# FX-Devcart_rev_A.net
KiCad netlist of a schematic drawn in EAGLE
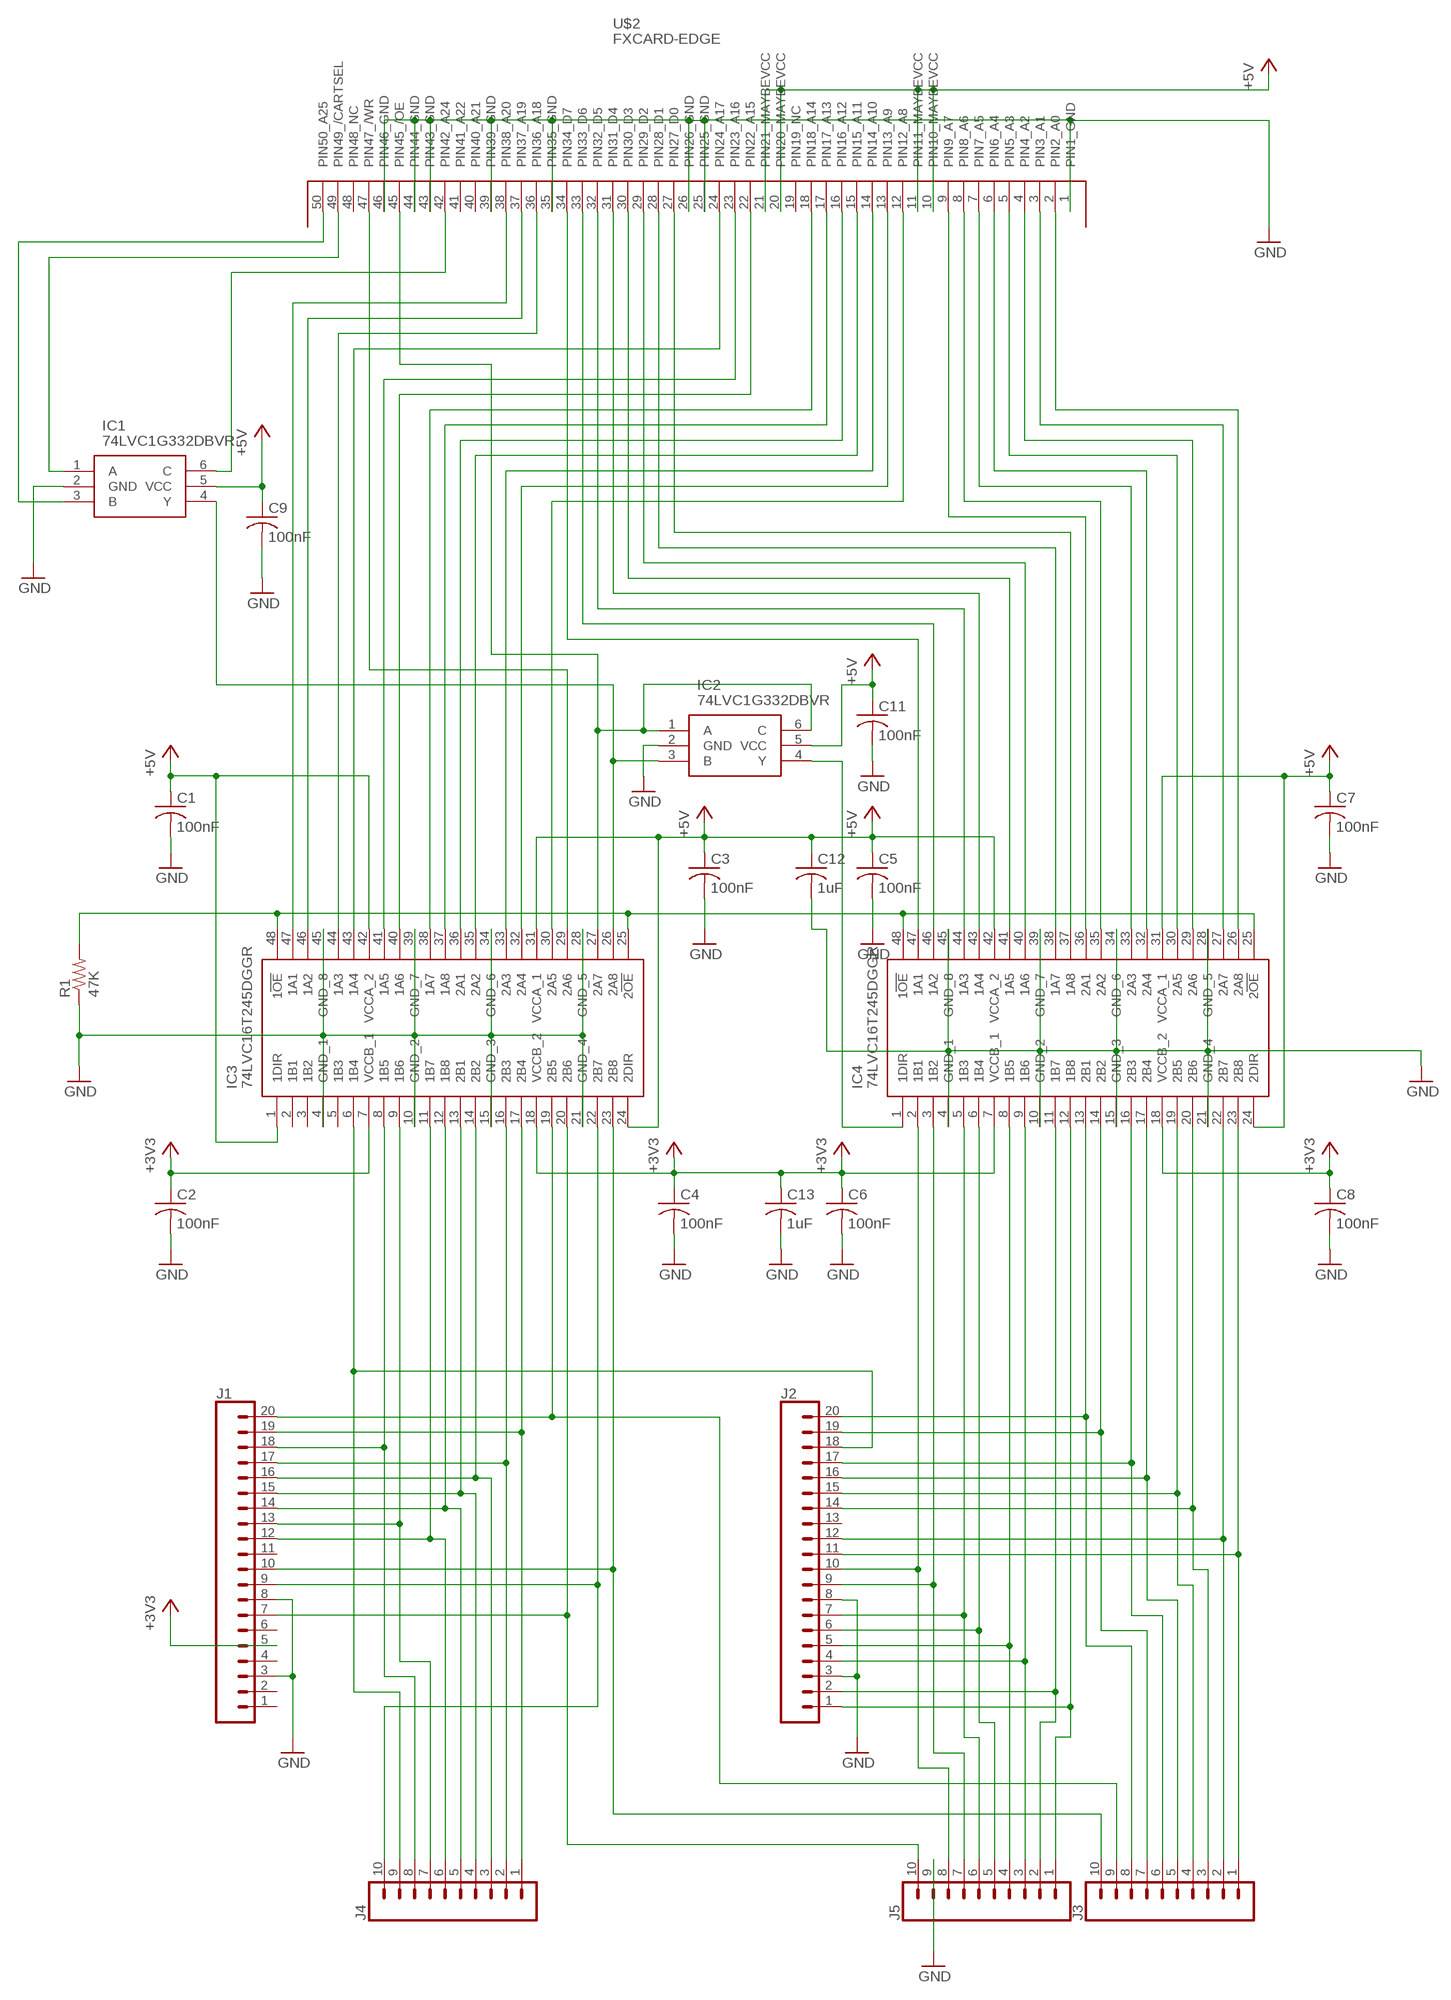
[diagram p0: schematic, sheet 1]

(export (version "E")
  (design (tool "Eeschema 10.0.6"))
  (components
    (comp (ref "C1")
      (value "100nF")
      (footprint "eagle-import:C0402")
      (libsource (lib "eagle-import") (part "C-USC0402"))
    )
    (comp (ref "C2")
      (value "100nF")
      (footprint "eagle-import:C0402")
      (libsource (lib "eagle-import") (part "C-USC0402"))
    )
    (comp (ref "C3")
      (value "100nF")
      (footprint "eagle-import:C0402")
      (libsource (lib "eagle-import") (part "C-USC0402"))
    )
    (comp (ref "C4")
      (value "100nF")
      (footprint "eagle-import:C0402")
      (libsource (lib "eagle-import") (part "C-USC0402"))
    )
    (comp (ref "C5")
      (value "100nF")
      (footprint "eagle-import:C0402")
      (libsource (lib "eagle-import") (part "C-USC0402"))
    )
    (comp (ref "C6")
      (value "100nF")
      (footprint "eagle-import:C0402")
      (libsource (lib "eagle-import") (part "C-USC0402"))
    )
    (comp (ref "C7")
      (value "100nF")
      (footprint "eagle-import:C0402")
      (libsource (lib "eagle-import") (part "C-USC0402"))
    )
    (comp (ref "C8")
      (value "100nF")
      (footprint "eagle-import:C0402")
      (libsource (lib "eagle-import") (part "C-USC0402"))
    )
    (comp (ref "C9")
      (value "100nF")
      (footprint "eagle-import:C0402")
      (libsource (lib "eagle-import") (part "C-USC0402"))
    )
    (comp (ref "C11")
      (value "100nF")
      (footprint "eagle-import:C0402")
      (libsource (lib "eagle-import") (part "C-USC0402"))
    )
    (comp (ref "C12")
      (value "1uF")
      (footprint "eagle-import:C0402")
      (libsource (lib "eagle-import") (part "C-USC0402"))
    )
    (comp (ref "C13")
      (value "1uF")
      (footprint "eagle-import:C0402")
      (libsource (lib "eagle-import") (part "C-USC0402"))
    )
    (comp (ref "IC1")
      (value "74LVC1G332DBVR")
      (footprint "eagle-import:SOT95P280X145-6N")
      (libsource (lib "eagle-import") (part "74LVC1G332DBVR"))
    )
    (comp (ref "IC2")
      (value "74LVC1G332DBVR")
      (footprint "eagle-import:SOT95P280X145-6N")
      (libsource (lib "eagle-import") (part "74LVC1G332DBVR"))
    )
    (comp (ref "IC3")
      (value "74LVC16T245DGGR")
      (footprint "eagle-import:SOP50P810X120-48N")
      (libsource (lib "eagle-import") (part "74LVC16T245DGGR"))
    )
    (comp (ref "IC4")
      (value "74LVC16T245DGGR")
      (footprint "eagle-import:SOP50P810X120-48N")
      (libsource (lib "eagle-import") (part "74LVC16T245DGGR"))
    )
    (comp (ref "J1")
      (value "CONN_20NOSILK")
      (footprint "eagle-import:1X20_NOSILK")
      (libsource (lib "eagle-import") (part "CONN_20NOSILK"))
    )
    (comp (ref "J2")
      (value "CONN_20NOSILK")
      (footprint "eagle-import:1X20_NOSILK")
      (libsource (lib "eagle-import") (part "CONN_20NOSILK"))
    )
    (comp (ref "J3")
      (value "CONN_10NO_SILK_PTH_FEMALE")
      (footprint "eagle-import:1X10_NO_SILK")
      (libsource (lib "eagle-import") (part "CONN_10NO_SILK_PTH_FEMALE"))
    )
    (comp (ref "J4")
      (value "CONN_10NO_SILK_PTH_FEMALE")
      (footprint "eagle-import:1X10_NO_SILK")
      (libsource (lib "eagle-import") (part "CONN_10NO_SILK_PTH_FEMALE"))
    )
    (comp (ref "J5")
      (value "CONN_10NO_SILK_PTH_FEMALE")
      (footprint "eagle-import:1X10_NO_SILK")
      (libsource (lib "eagle-import") (part "CONN_10NO_SILK_PTH_FEMALE"))
    )
    (comp (ref "R1")
      (value "47K")
      (footprint "eagle-import:R0402")
      (libsource (lib "eagle-import") (part "R-US_R0402"))
    )
    (comp (ref "U$2")
      (value "FXCARD-EDGE")
      (footprint "eagle-import:FXCARD-EDGE")
      (libsource (lib "eagle-import") (part "FXCARD-EDGE"))
    )
  )
  (nets
    (net (code "1") (name "+3V3") (class "Default")
      (node (ref "C13") (pin "1") (pinfunction "1_1") (pintype "passive"))
      (node (ref "C2") (pin "1") (pinfunction "1_1") (pintype "passive"))
      (node (ref "C4") (pin "1") (pinfunction "1_1") (pintype "passive"))
      (node (ref "C6") (pin "1") (pinfunction "1_1") (pintype "passive"))
      (node (ref "C8") (pin "1") (pinfunction "1_1") (pintype "passive"))
      (node (ref "IC3") (pin "18") (pinfunction "VCCB_2_18") (pintype "bidirectional"))
      (node (ref "IC3") (pin "7") (pinfunction "VCCB_1_7") (pintype "bidirectional"))
      (node (ref "IC4") (pin "18") (pinfunction "VCCB_2_18") (pintype "bidirectional"))
      (node (ref "IC4") (pin "7") (pinfunction "VCCB_1_7") (pintype "bidirectional"))
      (node (ref "J1") (pin "5") (pinfunction "5_5") (pintype "passive"))
    )
    (net (code "2") (name "+5V") (class "Default")
      (node (ref "C1") (pin "1") (pinfunction "1_1") (pintype "passive"))
      (node (ref "C11") (pin "1") (pinfunction "1_1") (pintype "passive"))
      (node (ref "C12") (pin "1") (pinfunction "1_1") (pintype "passive"))
      (node (ref "C3") (pin "1") (pinfunction "1_1") (pintype "passive"))
      (node (ref "C5") (pin "1") (pinfunction "1_1") (pintype "passive"))
      (node (ref "C7") (pin "1") (pinfunction "1_1") (pintype "passive"))
      (node (ref "C9") (pin "1") (pinfunction "1_1") (pintype "passive"))
      (node (ref "IC1") (pin "5") (pinfunction "VCC_5") (pintype "bidirectional"))
      (node (ref "IC2") (pin "5") (pinfunction "VCC_5") (pintype "bidirectional"))
      (node (ref "IC3") (pin "1") (pinfunction "1DIR_1") (pintype "bidirectional"))
      (node (ref "IC3") (pin "24") (pinfunction "2DIR_24") (pintype "bidirectional"))
      (node (ref "IC3") (pin "31") (pinfunction "VCCA_1_31") (pintype "bidirectional"))
      (node (ref "IC3") (pin "42") (pinfunction "VCCA_2_42") (pintype "bidirectional"))
      (node (ref "IC4") (pin "24") (pinfunction "2DIR_24") (pintype "bidirectional"))
      (node (ref "IC4") (pin "31") (pinfunction "VCCA_1_31") (pintype "bidirectional"))
      (node (ref "IC4") (pin "42") (pinfunction "VCCA_2_42") (pintype "bidirectional"))
      (node (ref "U$2") (pin "10") (pinfunction "PIN10_MAYBEVCC_10") (pintype "bidirectional"))
      (node (ref "U$2") (pin "11") (pinfunction "PIN11_MAYBEVCC_11") (pintype "bidirectional"))
      (node (ref "U$2") (pin "20") (pinfunction "PIN20_MAYBEVCC_20") (pintype "bidirectional"))
      (node (ref "U$2") (pin "21") (pinfunction "PIN21_MAYBEVCC_21") (pintype "bidirectional"))
    )
    (net (code "3") (name "GND") (class "Default")
      (node (ref "C1") (pin "2") (pinfunction "2_2") (pintype "passive"))
      (node (ref "C11") (pin "2") (pinfunction "2_2") (pintype "passive"))
      (node (ref "C12") (pin "2") (pinfunction "2_2") (pintype "passive"))
      (node (ref "C13") (pin "2") (pinfunction "2_2") (pintype "passive"))
      (node (ref "C2") (pin "2") (pinfunction "2_2") (pintype "passive"))
      (node (ref "C3") (pin "2") (pinfunction "2_2") (pintype "passive"))
      (node (ref "C4") (pin "2") (pinfunction "2_2") (pintype "passive"))
      (node (ref "C5") (pin "2") (pinfunction "2_2") (pintype "passive"))
      (node (ref "C6") (pin "2") (pinfunction "2_2") (pintype "passive"))
      (node (ref "C7") (pin "2") (pinfunction "2_2") (pintype "passive"))
      (node (ref "C8") (pin "2") (pinfunction "2_2") (pintype "passive"))
      (node (ref "C9") (pin "2") (pinfunction "2_2") (pintype "passive"))
      (node (ref "IC1") (pin "2") (pinfunction "GND_2") (pintype "bidirectional"))
      (node (ref "IC2") (pin "2") (pinfunction "GND_2") (pintype "bidirectional"))
      (node (ref "IC3") (pin "10") (pinfunction "GND_2_10") (pintype "bidirectional"))
      (node (ref "IC3") (pin "15") (pinfunction "GND_3_15") (pintype "bidirectional"))
      (node (ref "IC3") (pin "21") (pinfunction "GND_4_21") (pintype "bidirectional"))
      (node (ref "IC3") (pin "28") (pinfunction "GND_5_28") (pintype "bidirectional"))
      (node (ref "IC3") (pin "34") (pinfunction "GND_6_34") (pintype "bidirectional"))
      (node (ref "IC3") (pin "39") (pinfunction "GND_7_39") (pintype "bidirectional"))
      (node (ref "IC3") (pin "4") (pinfunction "GND_1_4") (pintype "bidirectional"))
      (node (ref "IC3") (pin "45") (pinfunction "GND_8_45") (pintype "bidirectional"))
      (node (ref "IC4") (pin "10") (pinfunction "GND_2_10") (pintype "bidirectional"))
      (node (ref "IC4") (pin "15") (pinfunction "GND_3_15") (pintype "bidirectional"))
      (node (ref "IC4") (pin "21") (pinfunction "GND_4_21") (pintype "bidirectional"))
      (node (ref "IC4") (pin "28") (pinfunction "GND_5_28") (pintype "bidirectional"))
      (node (ref "IC4") (pin "34") (pinfunction "GND_6_34") (pintype "bidirectional"))
      (node (ref "IC4") (pin "39") (pinfunction "GND_7_39") (pintype "bidirectional"))
      (node (ref "IC4") (pin "4") (pinfunction "GND_1_4") (pintype "bidirectional"))
      (node (ref "IC4") (pin "45") (pinfunction "GND_8_45") (pintype "bidirectional"))
      (node (ref "J1") (pin "3") (pinfunction "3_3") (pintype "passive"))
      (node (ref "J1") (pin "8") (pinfunction "8_8") (pintype "passive"))
      (node (ref "J2") (pin "3") (pinfunction "3_3") (pintype "passive"))
      (node (ref "J2") (pin "8") (pinfunction "8_8") (pintype "passive"))
      (node (ref "J5") (pin "9") (pinfunction "9_9") (pintype "passive"))
      (node (ref "R1") (pin "1") (pinfunction "1_1") (pintype "passive"))
      (node (ref "U$2") (pin "1") (pinfunction "PIN1_GND_1") (pintype "power_in"))
      (node (ref "U$2") (pin "25") (pinfunction "PIN25_GND_25") (pintype "power_in"))
      (node (ref "U$2") (pin "26") (pinfunction "PIN26_GND_26") (pintype "power_in"))
      (node (ref "U$2") (pin "35") (pinfunction "PIN35_GND_35") (pintype "power_in"))
      (node (ref "U$2") (pin "39") (pinfunction "PIN39_GND_39") (pintype "power_in"))
      (node (ref "U$2") (pin "43") (pinfunction "PIN43_GND_43") (pintype "power_in"))
      (node (ref "U$2") (pin "44") (pinfunction "PIN44_GND_44") (pintype "power_in"))
      (node (ref "U$2") (pin "46") (pinfunction "PIN46_GND_46") (pintype "power_in"))
    )
    (net (code "4") (name "Net-(IC1-A)") (class "Default")
      (node (ref "IC1") (pin "1") (pinfunction "A_1") (pintype "bidirectional"))
      (node (ref "U$2") (pin "49") (pinfunction "PIN49_/CARTSEL_49") (pintype "bidirectional"))
    )
    (net (code "5") (name "Net-(IC1-B)") (class "Default")
      (node (ref "IC1") (pin "3") (pinfunction "B_3") (pintype "bidirectional"))
      (node (ref "U$2") (pin "50") (pinfunction "PIN50_A25_50") (pintype "bidirectional"))
    )
    (net (code "6") (name "Net-(IC1-C)") (class "Default")
      (node (ref "IC1") (pin "6") (pinfunction "C_6") (pintype "bidirectional"))
      (node (ref "U$2") (pin "42") (pinfunction "PIN42_A24_42") (pintype "bidirectional"))
    )
    (net (code "7") (name "Net-(IC1-Y)") (class "Default")
      (node (ref "IC1") (pin "4") (pinfunction "Y_4") (pintype "bidirectional"))
      (node (ref "IC2") (pin "3") (pinfunction "B_3") (pintype "bidirectional"))
      (node (ref "IC3") (pin "26") (pinfunction "2A8_26") (pintype "bidirectional"))
    )
    (net (code "8") (name "Net-(IC2-A)") (class "Default")
      (node (ref "IC2") (pin "1") (pinfunction "A_1") (pintype "bidirectional"))
      (node (ref "IC2") (pin "6") (pinfunction "C_6") (pintype "bidirectional"))
      (node (ref "IC3") (pin "27") (pinfunction "2A7_27") (pintype "bidirectional"))
      (node (ref "U$2") (pin "45") (pinfunction "PIN45_/OE_45") (pintype "bidirectional"))
    )
    (net (code "9") (name "Net-(IC2-Y)") (class "Default")
      (node (ref "IC2") (pin "4") (pinfunction "Y_4") (pintype "bidirectional"))
      (node (ref "IC4") (pin "1") (pinfunction "1DIR_1") (pintype "bidirectional"))
    )
    (net (code "10") (name "Net-(IC3-1A1)") (class "Default")
      (node (ref "IC3") (pin "47") (pinfunction "1A1_47") (pintype "bidirectional"))
      (node (ref "U$2") (pin "38") (pinfunction "PIN38_A20_38") (pintype "bidirectional"))
    )
    (net (code "11") (name "Net-(IC3-1A2)") (class "Default")
      (node (ref "IC3") (pin "46") (pinfunction "1A2_46") (pintype "bidirectional"))
      (node (ref "U$2") (pin "37") (pinfunction "PIN37_A19_37") (pintype "bidirectional"))
    )
    (net (code "12") (name "Net-(IC3-1A3)") (class "Default")
      (node (ref "IC3") (pin "44") (pinfunction "1A3_44") (pintype "bidirectional"))
      (node (ref "U$2") (pin "36") (pinfunction "PIN36_A18_36") (pintype "bidirectional"))
    )
    (net (code "13") (name "Net-(IC3-1A4)") (class "Default")
      (node (ref "IC3") (pin "43") (pinfunction "1A4_43") (pintype "bidirectional"))
      (node (ref "U$2") (pin "24") (pinfunction "PIN24_A17_24") (pintype "bidirectional"))
    )
    (net (code "14") (name "Net-(IC3-1A5)") (class "Default")
      (node (ref "IC3") (pin "41") (pinfunction "1A5_41") (pintype "bidirectional"))
      (node (ref "U$2") (pin "23") (pinfunction "PIN23_A16_23") (pintype "bidirectional"))
    )
    (net (code "15") (name "Net-(IC3-1A6)") (class "Default")
      (node (ref "IC3") (pin "40") (pinfunction "1A6_40") (pintype "bidirectional"))
      (node (ref "U$2") (pin "22") (pinfunction "PIN22_A15_22") (pintype "bidirectional"))
    )
    (net (code "16") (name "Net-(IC3-1A7)") (class "Default")
      (node (ref "IC3") (pin "38") (pinfunction "1A7_38") (pintype "bidirectional"))
      (node (ref "U$2") (pin "18") (pinfunction "PIN18_A14_18") (pintype "bidirectional"))
    )
    (net (code "17") (name "Net-(IC3-1A8)") (class "Default")
      (node (ref "IC3") (pin "37") (pinfunction "1A8_37") (pintype "bidirectional"))
      (node (ref "U$2") (pin "17") (pinfunction "PIN17_A13_17") (pintype "bidirectional"))
    )
    (net (code "18") (name "Net-(IC3-1B4)") (class "Default")
      (node (ref "IC3") (pin "6") (pinfunction "1B4_6") (pintype "bidirectional"))
      (node (ref "J2") (pin "18") (pinfunction "18_18") (pintype "passive"))
      (node (ref "J4") (pin "9") (pinfunction "9_9") (pintype "passive"))
    )
    (net (code "19") (name "Net-(IC3-1B5)") (class "Default")
      (node (ref "IC3") (pin "8") (pinfunction "1B5_8") (pintype "bidirectional"))
      (node (ref "J1") (pin "18") (pinfunction "18_18") (pintype "passive"))
      (node (ref "J4") (pin "8") (pinfunction "8_8") (pintype "passive"))
    )
    (net (code "20") (name "Net-(IC3-1B6)") (class "Default")
      (node (ref "IC3") (pin "9") (pinfunction "1B6_9") (pintype "bidirectional"))
      (node (ref "J1") (pin "13") (pinfunction "13_13") (pintype "passive"))
      (node (ref "J4") (pin "7") (pinfunction "7_7") (pintype "passive"))
    )
    (net (code "21") (name "Net-(IC3-1B7)") (class "Default")
      (node (ref "IC3") (pin "11") (pinfunction "1B7_11") (pintype "bidirectional"))
      (node (ref "J1") (pin "12") (pinfunction "12_12") (pintype "passive"))
      (node (ref "J4") (pin "6") (pinfunction "6_6") (pintype "passive"))
    )
    (net (code "22") (name "Net-(IC3-1B8)") (class "Default")
      (node (ref "IC3") (pin "12") (pinfunction "1B8_12") (pintype "bidirectional"))
      (node (ref "J1") (pin "14") (pinfunction "14_14") (pintype "passive"))
      (node (ref "J4") (pin "5") (pinfunction "5_5") (pintype "passive"))
    )
    (net (code "23") (name "Net-(IC3-1~{OE})") (class "Default")
      (node (ref "IC3") (pin "25") (pinfunction "2~{OE}_25") (pintype "bidirectional"))
      (node (ref "IC3") (pin "48") (pinfunction "1~{OE}_48") (pintype "bidirectional"))
      (node (ref "IC4") (pin "25") (pinfunction "2~{OE}_25") (pintype "bidirectional"))
      (node (ref "IC4") (pin "48") (pinfunction "1~{OE}_48") (pintype "bidirectional"))
      (node (ref "R1") (pin "2") (pinfunction "2_2") (pintype "passive"))
    )
    (net (code "24") (name "Net-(IC3-2A1)") (class "Default")
      (node (ref "IC3") (pin "36") (pinfunction "2A1_36") (pintype "bidirectional"))
      (node (ref "U$2") (pin "16") (pinfunction "PIN16_A12_16") (pintype "bidirectional"))
    )
    (net (code "25") (name "Net-(IC3-2A2)") (class "Default")
      (node (ref "IC3") (pin "35") (pinfunction "2A2_35") (pintype "bidirectional"))
      (node (ref "U$2") (pin "15") (pinfunction "PIN15_A11_15") (pintype "bidirectional"))
    )
    (net (code "26") (name "Net-(IC3-2A3)") (class "Default")
      (node (ref "IC3") (pin "33") (pinfunction "2A3_33") (pintype "bidirectional"))
      (node (ref "U$2") (pin "14") (pinfunction "PIN14_A10_14") (pintype "bidirectional"))
    )
    (net (code "27") (name "Net-(IC3-2A4)") (class "Default")
      (node (ref "IC3") (pin "32") (pinfunction "2A4_32") (pintype "bidirectional"))
      (node (ref "U$2") (pin "13") (pinfunction "PIN13_A9_13") (pintype "bidirectional"))
    )
    (net (code "28") (name "Net-(IC3-2A5)") (class "Default")
      (node (ref "IC3") (pin "30") (pinfunction "2A5_30") (pintype "bidirectional"))
      (node (ref "U$2") (pin "12") (pinfunction "PIN12_A8_12") (pintype "bidirectional"))
    )
    (net (code "29") (name "Net-(IC3-2A6)") (class "Default")
      (node (ref "IC3") (pin "29") (pinfunction "2A6_29") (pintype "bidirectional"))
      (node (ref "U$2") (pin "47") (pinfunction "PIN47_/WR_47") (pintype "bidirectional"))
    )
    (net (code "30") (name "Net-(IC3-2B1)") (class "Default")
      (node (ref "IC3") (pin "13") (pinfunction "2B1_13") (pintype "bidirectional"))
      (node (ref "J1") (pin "15") (pinfunction "15_15") (pintype "passive"))
      (node (ref "J4") (pin "4") (pinfunction "4_4") (pintype "passive"))
    )
    (net (code "31") (name "Net-(IC3-2B2)") (class "Default")
      (node (ref "IC3") (pin "14") (pinfunction "2B2_14") (pintype "bidirectional"))
      (node (ref "J1") (pin "16") (pinfunction "16_16") (pintype "passive"))
      (node (ref "J4") (pin "3") (pinfunction "3_3") (pintype "passive"))
    )
    (net (code "32") (name "Net-(IC3-2B3)") (class "Default")
      (node (ref "IC3") (pin "16") (pinfunction "2B3_16") (pintype "bidirectional"))
      (node (ref "J1") (pin "17") (pinfunction "17_17") (pintype "passive"))
      (node (ref "J4") (pin "2") (pinfunction "2_2") (pintype "passive"))
    )
    (net (code "33") (name "Net-(IC3-2B4)") (class "Default")
      (node (ref "IC3") (pin "17") (pinfunction "2B4_17") (pintype "bidirectional"))
      (node (ref "J1") (pin "19") (pinfunction "19_19") (pintype "passive"))
      (node (ref "J4") (pin "1") (pinfunction "1_1") (pintype "passive"))
    )
    (net (code "34") (name "Net-(IC3-2B5)") (class "Default")
      (node (ref "IC3") (pin "19") (pinfunction "2B5_19") (pintype "bidirectional"))
      (node (ref "J1") (pin "20") (pinfunction "20_20") (pintype "passive"))
      (node (ref "J3") (pin "9") (pinfunction "9_9") (pintype "passive"))
    )
    (net (code "35") (name "Net-(IC3-2B6)") (class "Default")
      (node (ref "IC3") (pin "20") (pinfunction "2B6_20") (pintype "bidirectional"))
      (node (ref "J1") (pin "7") (pinfunction "7_7") (pintype "passive"))
      (node (ref "J5") (pin "10") (pinfunction "10_10") (pintype "passive"))
    )
    (net (code "36") (name "Net-(IC3-2B7)") (class "Default")
      (node (ref "IC3") (pin "22") (pinfunction "2B7_22") (pintype "bidirectional"))
      (node (ref "J1") (pin "9") (pinfunction "9_9") (pintype "passive"))
      (node (ref "J4") (pin "10") (pinfunction "10_10") (pintype "passive"))
    )
    (net (code "37") (name "Net-(IC3-2B8)") (class "Default")
      (node (ref "IC3") (pin "23") (pinfunction "2B8_23") (pintype "bidirectional"))
      (node (ref "J1") (pin "10") (pinfunction "10_10") (pintype "passive"))
      (node (ref "J3") (pin "10") (pinfunction "10_10") (pintype "passive"))
    )
    (net (code "38") (name "Net-(IC4-1A1)") (class "Default")
      (node (ref "IC4") (pin "47") (pinfunction "1A1_47") (pintype "bidirectional"))
      (node (ref "U$2") (pin "34") (pinfunction "PIN34_D7_34") (pintype "bidirectional"))
    )
    (net (code "39") (name "Net-(IC4-1A2)") (class "Default")
      (node (ref "IC4") (pin "46") (pinfunction "1A2_46") (pintype "bidirectional"))
      (node (ref "U$2") (pin "33") (pinfunction "PIN33_D6_33") (pintype "bidirectional"))
    )
    (net (code "40") (name "Net-(IC4-1A3)") (class "Default")
      (node (ref "IC4") (pin "44") (pinfunction "1A3_44") (pintype "bidirectional"))
      (node (ref "U$2") (pin "32") (pinfunction "PIN32_D5_32") (pintype "bidirectional"))
    )
    (net (code "41") (name "Net-(IC4-1A4)") (class "Default")
      (node (ref "IC4") (pin "43") (pinfunction "1A4_43") (pintype "bidirectional"))
      (node (ref "U$2") (pin "31") (pinfunction "PIN31_D4_31") (pintype "bidirectional"))
    )
    (net (code "42") (name "Net-(IC4-1A5)") (class "Default")
      (node (ref "IC4") (pin "41") (pinfunction "1A5_41") (pintype "bidirectional"))
      (node (ref "U$2") (pin "30") (pinfunction "PIN30_D3_30") (pintype "bidirectional"))
    )
    (net (code "43") (name "Net-(IC4-1A6)") (class "Default")
      (node (ref "IC4") (pin "40") (pinfunction "1A6_40") (pintype "bidirectional"))
      (node (ref "U$2") (pin "29") (pinfunction "PIN29_D2_29") (pintype "bidirectional"))
    )
    (net (code "44") (name "Net-(IC4-1A7)") (class "Default")
      (node (ref "IC4") (pin "38") (pinfunction "1A7_38") (pintype "bidirectional"))
      (node (ref "U$2") (pin "28") (pinfunction "PIN28_D1_28") (pintype "bidirectional"))
    )
    (net (code "45") (name "Net-(IC4-1A8)") (class "Default")
      (node (ref "IC4") (pin "37") (pinfunction "1A8_37") (pintype "bidirectional"))
      (node (ref "U$2") (pin "27") (pinfunction "PIN27_D0_27") (pintype "bidirectional"))
    )
    (net (code "46") (name "Net-(IC4-1B1)") (class "Default")
      (node (ref "IC4") (pin "2") (pinfunction "1B1_2") (pintype "bidirectional"))
      (node (ref "J2") (pin "10") (pinfunction "10_10") (pintype "passive"))
      (node (ref "J5") (pin "8") (pinfunction "8_8") (pintype "passive"))
    )
    (net (code "47") (name "Net-(IC4-1B2)") (class "Default")
      (node (ref "IC4") (pin "3") (pinfunction "1B2_3") (pintype "bidirectional"))
      (node (ref "J2") (pin "9") (pinfunction "9_9") (pintype "passive"))
      (node (ref "J5") (pin "7") (pinfunction "7_7") (pintype "passive"))
    )
    (net (code "48") (name "Net-(IC4-1B3)") (class "Default")
      (node (ref "IC4") (pin "5") (pinfunction "1B3_5") (pintype "bidirectional"))
      (node (ref "J2") (pin "7") (pinfunction "7_7") (pintype "passive"))
      (node (ref "J5") (pin "6") (pinfunction "6_6") (pintype "passive"))
    )
    (net (code "49") (name "Net-(IC4-1B4)") (class "Default")
      (node (ref "IC4") (pin "6") (pinfunction "1B4_6") (pintype "bidirectional"))
      (node (ref "J2") (pin "6") (pinfunction "6_6") (pintype "passive"))
      (node (ref "J5") (pin "5") (pinfunction "5_5") (pintype "passive"))
    )
    (net (code "50") (name "Net-(IC4-1B5)") (class "Default")
      (node (ref "IC4") (pin "8") (pinfunction "1B5_8") (pintype "bidirectional"))
      (node (ref "J2") (pin "5") (pinfunction "5_5") (pintype "passive"))
      (node (ref "J5") (pin "4") (pinfunction "4_4") (pintype "passive"))
    )
    (net (code "51") (name "Net-(IC4-1B6)") (class "Default")
      (node (ref "IC4") (pin "9") (pinfunction "1B6_9") (pintype "bidirectional"))
      (node (ref "J2") (pin "4") (pinfunction "4_4") (pintype "passive"))
      (node (ref "J5") (pin "3") (pinfunction "3_3") (pintype "passive"))
    )
    (net (code "52") (name "Net-(IC4-1B7)") (class "Default")
      (node (ref "IC4") (pin "11") (pinfunction "1B7_11") (pintype "bidirectional"))
      (node (ref "J2") (pin "2") (pinfunction "2_2") (pintype "passive"))
      (node (ref "J5") (pin "2") (pinfunction "2_2") (pintype "passive"))
    )
    (net (code "53") (name "Net-(IC4-1B8)") (class "Default")
      (node (ref "IC4") (pin "12") (pinfunction "1B8_12") (pintype "bidirectional"))
      (node (ref "J2") (pin "1") (pinfunction "1_1") (pintype "passive"))
      (node (ref "J5") (pin "1") (pinfunction "1_1") (pintype "passive"))
    )
    (net (code "54") (name "Net-(IC4-2A1)") (class "Default")
      (node (ref "IC4") (pin "36") (pinfunction "2A1_36") (pintype "bidirectional"))
      (node (ref "U$2") (pin "9") (pinfunction "PIN9_A7_9") (pintype "bidirectional"))
    )
    (net (code "55") (name "Net-(IC4-2A2)") (class "Default")
      (node (ref "IC4") (pin "35") (pinfunction "2A2_35") (pintype "bidirectional"))
      (node (ref "U$2") (pin "8") (pinfunction "PIN8_A6_8") (pintype "bidirectional"))
    )
    (net (code "56") (name "Net-(IC4-2A3)") (class "Default")
      (node (ref "IC4") (pin "33") (pinfunction "2A3_33") (pintype "bidirectional"))
      (node (ref "U$2") (pin "7") (pinfunction "PIN7_A5_7") (pintype "bidirectional"))
    )
    (net (code "57") (name "Net-(IC4-2A4)") (class "Default")
      (node (ref "IC4") (pin "32") (pinfunction "2A4_32") (pintype "bidirectional"))
      (node (ref "U$2") (pin "6") (pinfunction "PIN6_A4_6") (pintype "bidirectional"))
    )
    (net (code "58") (name "Net-(IC4-2A5)") (class "Default")
      (node (ref "IC4") (pin "30") (pinfunction "2A5_30") (pintype "bidirectional"))
      (node (ref "U$2") (pin "5") (pinfunction "PIN5_A3_5") (pintype "bidirectional"))
    )
    (net (code "59") (name "Net-(IC4-2A6)") (class "Default")
      (node (ref "IC4") (pin "29") (pinfunction "2A6_29") (pintype "bidirectional"))
      (node (ref "U$2") (pin "4") (pinfunction "PIN4_A2_4") (pintype "bidirectional"))
    )
    (net (code "60") (name "Net-(IC4-2A7)") (class "Default")
      (node (ref "IC4") (pin "27") (pinfunction "2A7_27") (pintype "bidirectional"))
      (node (ref "U$2") (pin "3") (pinfunction "PIN3_A1_3") (pintype "bidirectional"))
    )
    (net (code "61") (name "Net-(IC4-2A8)") (class "Default")
      (node (ref "IC4") (pin "26") (pinfunction "2A8_26") (pintype "bidirectional"))
      (node (ref "U$2") (pin "2") (pinfunction "PIN2_A0_2") (pintype "bidirectional"))
    )
    (net (code "62") (name "Net-(IC4-2B1)") (class "Default")
      (node (ref "IC4") (pin "13") (pinfunction "2B1_13") (pintype "bidirectional"))
      (node (ref "J2") (pin "20") (pinfunction "20_20") (pintype "passive"))
      (node (ref "J3") (pin "8") (pinfunction "8_8") (pintype "passive"))
    )
    (net (code "63") (name "Net-(IC4-2B2)") (class "Default")
      (node (ref "IC4") (pin "14") (pinfunction "2B2_14") (pintype "bidirectional"))
      (node (ref "J2") (pin "19") (pinfunction "19_19") (pintype "passive"))
      (node (ref "J3") (pin "7") (pinfunction "7_7") (pintype "passive"))
    )
    (net (code "64") (name "Net-(IC4-2B3)") (class "Default")
      (node (ref "IC4") (pin "16") (pinfunction "2B3_16") (pintype "bidirectional"))
      (node (ref "J2") (pin "17") (pinfunction "17_17") (pintype "passive"))
      (node (ref "J3") (pin "6") (pinfunction "6_6") (pintype "passive"))
    )
    (net (code "65") (name "Net-(IC4-2B4)") (class "Default")
      (node (ref "IC4") (pin "17") (pinfunction "2B4_17") (pintype "bidirectional"))
      (node (ref "J2") (pin "16") (pinfunction "16_16") (pintype "passive"))
      (node (ref "J3") (pin "5") (pinfunction "5_5") (pintype "passive"))
    )
    (net (code "66") (name "Net-(IC4-2B5)") (class "Default")
      (node (ref "IC4") (pin "19") (pinfunction "2B5_19") (pintype "bidirectional"))
      (node (ref "J2") (pin "15") (pinfunction "15_15") (pintype "passive"))
      (node (ref "J3") (pin "4") (pinfunction "4_4") (pintype "passive"))
    )
    (net (code "67") (name "Net-(IC4-2B6)") (class "Default")
      (node (ref "IC4") (pin "20") (pinfunction "2B6_20") (pintype "bidirectional"))
      (node (ref "J2") (pin "14") (pinfunction "14_14") (pintype "passive"))
      (node (ref "J3") (pin "3") (pinfunction "3_3") (pintype "passive"))
    )
    (net (code "68") (name "Net-(IC4-2B7)") (class "Default")
      (node (ref "IC4") (pin "22") (pinfunction "2B7_22") (pintype "bidirectional"))
      (node (ref "J2") (pin "12") (pinfunction "12_12") (pintype "passive"))
      (node (ref "J3") (pin "2") (pinfunction "2_2") (pintype "passive"))
    )
    (net (code "69") (name "Net-(IC4-2B8)") (class "Default")
      (node (ref "IC4") (pin "23") (pinfunction "2B8_23") (pintype "bidirectional"))
      (node (ref "J2") (pin "11") (pinfunction "11_11") (pintype "passive"))
      (node (ref "J3") (pin "1") (pinfunction "1_1") (pintype "passive"))
    )
    (net (code "70") (name "unconnected-(IC3-1B1-Pad2)") (class "Default")
      (node (ref "IC3") (pin "2") (pinfunction "1B1_2") (pintype "bidirectional"))
    )
    (net (code "71") (name "unconnected-(IC3-1B2-Pad3)") (class "Default")
      (node (ref "IC3") (pin "3") (pinfunction "1B2_3") (pintype "bidirectional"))
    )
    (net (code "72") (name "unconnected-(IC3-1B3-Pad5)") (class "Default")
      (node (ref "IC3") (pin "5") (pinfunction "1B3_5") (pintype "bidirectional"))
    )
    (net (code "73") (name "unconnected-(J1-Pad1)") (class "Default")
      (node (ref "J1") (pin "1") (pinfunction "1_1") (pintype "passive"))
    )
    (net (code "74") (name "unconnected-(J1-Pad2)") (class "Default")
      (node (ref "J1") (pin "2") (pinfunction "2_2") (pintype "passive"))
    )
    (net (code "75") (name "unconnected-(J1-Pad4)") (class "Default")
      (node (ref "J1") (pin "4") (pinfunction "4_4") (pintype "passive"))
    )
    (net (code "76") (name "unconnected-(J1-Pad6)") (class "Default")
      (node (ref "J1") (pin "6") (pinfunction "6_6") (pintype "passive"))
    )
    (net (code "77") (name "unconnected-(J1-Pad11)") (class "Default")
      (node (ref "J1") (pin "11") (pinfunction "11_11") (pintype "passive"))
    )
    (net (code "78") (name "unconnected-(J2-Pad13)") (class "Default")
      (node (ref "J2") (pin "13") (pinfunction "13_13") (pintype "passive"))
    )
    (net (code "79") (name "unconnected-(U$2-PIN19_NC-Pad19)") (class "Default")
      (node (ref "U$2") (pin "19") (pinfunction "PIN19_NC_19") (pintype "bidirectional"))
    )
    (net (code "80") (name "unconnected-(U$2-PIN40_A21-Pad40)") (class "Default")
      (node (ref "U$2") (pin "40") (pinfunction "PIN40_A21_40") (pintype "bidirectional"))
    )
    (net (code "81") (name "unconnected-(U$2-PIN41_A22-Pad41)") (class "Default")
      (node (ref "U$2") (pin "41") (pinfunction "PIN41_A22_41") (pintype "bidirectional"))
    )
    (net (code "82") (name "unconnected-(U$2-PIN48_NC-Pad48)") (class "Default")
      (node (ref "U$2") (pin "48") (pinfunction "PIN48_NC_48") (pintype "bidirectional"))
    )
  )
)
